# esp-oled-thing.net
KiCad netlist of a schematic drawn in EAGLE
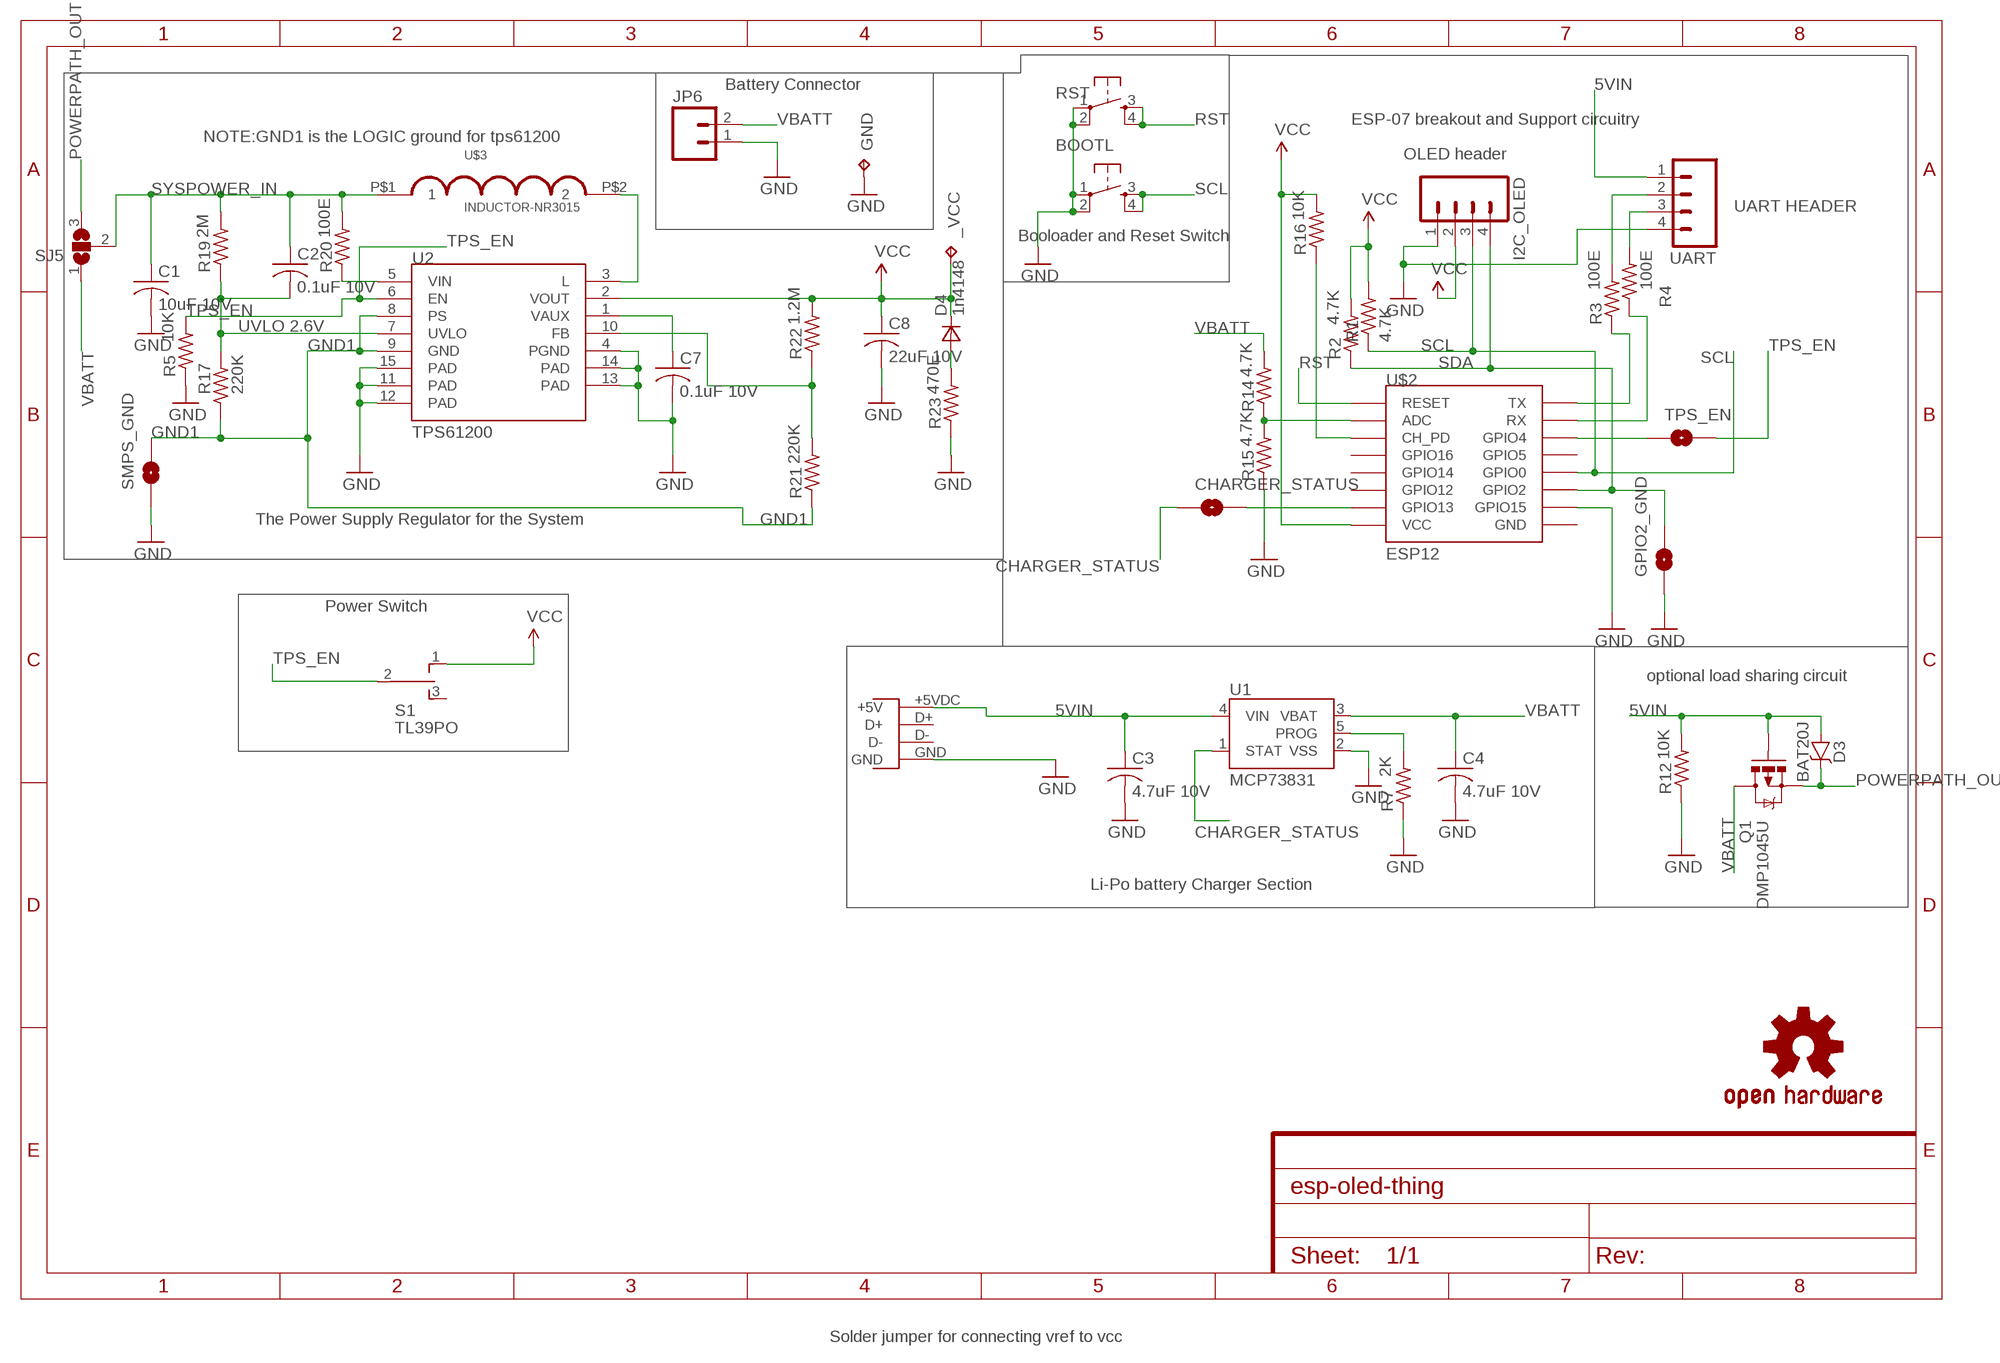
[diagram p0: schematic, sheet 1]

(export (version "E")
  (design (tool "Eeschema 10.0.6"))
  (components
    (comp (ref "BOOTL")
      (value "TAC_SWITCHSMD")
      (footprint "eagle-import:TACTILE_SWITCH_SMD")
      (libsource (lib "eagle-import") (part "TAC_SWITCHSMD"))
    )
    (comp (ref "C1")
      (value "10uF 10V")
      (footprint "eagle-import:C0805")
      (libsource (lib "eagle-import") (part "C-USC0805"))
    )
    (comp (ref "C2")
      (value "0.1uF 10V")
      (footprint "eagle-import:C0805")
      (libsource (lib "eagle-import") (part "C-USC0805"))
    )
    (comp (ref "C3")
      (value "4.7uF 10V")
      (footprint "eagle-import:C0805")
      (libsource (lib "eagle-import") (part "C-USC0805"))
    )
    (comp (ref "C4")
      (value "4.7uF 10V")
      (footprint "eagle-import:C0805")
      (libsource (lib "eagle-import") (part "C-USC0805"))
    )
    (comp (ref "C7")
      (value "0.1uF 10V")
      (footprint "eagle-import:C0805")
      (libsource (lib "eagle-import") (part "C-USC0805"))
    )
    (comp (ref "C8")
      (value "22uF 10V")
      (footprint "eagle-import:C0805")
      (libsource (lib "eagle-import") (part "C-USC0805"))
    )
    (comp (ref "CHARGER_STATUS")
      (value "SOLDERJUMPERNO")
      (footprint "eagle-import:SJ_2S-NO")
      (libsource (lib "eagle-import") (part "SOLDERJUMPERNO"))
    )
    (comp (ref "D3")
      (value "BAT20J")
      (footprint "eagle-import:SOD-323")
      (libsource (lib "eagle-import") (part "DIODE-SCHOTTKY-BAT20J"))
    )
    (comp (ref "D4")
      (value "1n4148")
      (footprint "eagle-import:SOD323")
      (fields (field (name "MPN") "CDSOD323-T05C"))
      (libsource (lib "eagle-import") (part "DSOD323"))
    )
    (comp (ref "GND")
      (value "TPTP10R")
      (footprint "eagle-import:TP10R")
      (libsource (lib "eagle-import") (part "TPTP10R"))
    )
    (comp (ref "GPIO2_GND")
      (value "SOLDERJUMPERNO")
      (footprint "eagle-import:SJ_2S-NO")
      (libsource (lib "eagle-import") (part "SOLDERJUMPERNO"))
    )
    (comp (ref "I2C_OLED")
      (value "M04PTH")
      (footprint "eagle-import:1X04")
      (libsource (lib "eagle-import") (part "M04PTH"))
    )
    (comp (ref "JP6")
      (value "M02JST-PTH-2")
      (footprint "eagle-import:JST-2-PTH")
      (libsource (lib "eagle-import") (part "M02JST-PTH-2"))
    )
    (comp (ref "Q1")
      (value "DMP1045U")
      (footprint "eagle-import:SOT23-3")
      (libsource (lib "eagle-import") (part "MOSFET-PCHANNELDMG2307L"))
    )
    (comp (ref "R1")
      (value "4.7K")
      (footprint "eagle-import:M0805")
      (libsource (lib "eagle-import") (part "R-US_M0805"))
    )
    (comp (ref "R2")
      (value "4.7K")
      (footprint "eagle-import:M0805")
      (libsource (lib "eagle-import") (part "R-US_M0805"))
    )
    (comp (ref "R3")
      (value "100E")
      (footprint "eagle-import:M0805")
      (libsource (lib "eagle-import") (part "R-US_M0805"))
    )
    (comp (ref "R4")
      (value "100E")
      (footprint "eagle-import:M0805")
      (libsource (lib "eagle-import") (part "R-US_M0805"))
    )
    (comp (ref "R5")
      (value "10K")
      (footprint "eagle-import:M0805")
      (libsource (lib "eagle-import") (part "R-US_M0805"))
    )
    (comp (ref "R7")
      (value "2K")
      (footprint "eagle-import:M0805")
      (libsource (lib "eagle-import") (part "R-US_M0805"))
    )
    (comp (ref "R12")
      (value "10K")
      (footprint "eagle-import:M0805")
      (libsource (lib "eagle-import") (part "R-US_M0805"))
    )
    (comp (ref "R14")
      (value "4.7K")
      (footprint "eagle-import:M0805")
      (libsource (lib "eagle-import") (part "R-US_M0805"))
    )
    (comp (ref "R15")
      (value "4.7K")
      (footprint "eagle-import:M0805")
      (libsource (lib "eagle-import") (part "R-US_M0805"))
    )
    (comp (ref "R16")
      (value "10K")
      (footprint "eagle-import:M0805")
      (libsource (lib "eagle-import") (part "R-US_M0805"))
    )
    (comp (ref "R17")
      (value "220K")
      (footprint "eagle-import:M0805")
      (libsource (lib "eagle-import") (part "R-US_M0805"))
    )
    (comp (ref "R19")
      (value "2M")
      (footprint "eagle-import:M0805")
      (libsource (lib "eagle-import") (part "R-US_M0805"))
    )
    (comp (ref "R20")
      (value "100E")
      (footprint "eagle-import:M0805")
      (libsource (lib "eagle-import") (part "R-US_M0805"))
    )
    (comp (ref "R21")
      (value "220K")
      (footprint "eagle-import:M0805")
      (libsource (lib "eagle-import") (part "R-US_M0805"))
    )
    (comp (ref "R22")
      (value "1.2M")
      (footprint "eagle-import:M0805")
      (libsource (lib "eagle-import") (part "R-US_M0805"))
    )
    (comp (ref "R23")
      (value "470E")
      (footprint "eagle-import:M0805")
      (libsource (lib "eagle-import") (part "R-US_M0805"))
    )
    (comp (ref "RST")
      (value "TAC_SWITCHSMD")
      (footprint "eagle-import:TACTILE_SWITCH_SMD")
      (libsource (lib "eagle-import") (part "TAC_SWITCHSMD"))
    )
    (comp (ref "S1")
      (value "TL39PO")
      (footprint "eagle-import:TL3XPO")
      (libsource (lib "eagle-import") (part "TL39PO"))
    )
    (comp (ref "SJ5")
      (value "SJ2W")
      (footprint "eagle-import:SJ_2")
      (libsource (lib "eagle-import") (part "SJ2W"))
    )
    (comp (ref "SMPS_GND")
      (value "SOLDERJUMPERNO")
      (footprint "eagle-import:SJ_2S-NO")
      (libsource (lib "eagle-import") (part "SOLDERJUMPERNO"))
    )
    (comp (ref "TPS_EN")
      (value "SOLDERJUMPERNO")
      (footprint "eagle-import:SJ_2S-NO")
      (libsource (lib "eagle-import") (part "SOLDERJUMPERNO"))
    )
    (comp (ref "U$1")
      (value "OSHW-LOGOS")
      (footprint "eagle-import:OSHW-LOGO-S")
      (libsource (lib "eagle-import") (part "OSHW-LOGOS"))
    )
    (comp (ref "U$2")
      (value "ESP12")
      (footprint "eagle-import:ESP12")
      (libsource (lib "eagle-import") (part "ESP12"))
    )
    (comp (ref "U$3")
      (value "INDUCTOR-NR3015")
      (footprint "eagle-import:INDUCTOR-NR3015")
      (libsource (lib "eagle-import") (part "INDUCTOR-NR3015"))
    )
    (comp (ref "U$4")
      (value "MICROUSB-MIDMOUNT")
      (footprint "eagle-import:MICROUSB-MIDMOUNT-MOLEX")
      (libsource (lib "eagle-import") (part "MICROUSB-MIDMOUNT"))
    )
    (comp (ref "U1")
      (value "MCP73831")
      (footprint "eagle-import:SOT23-5")
      (libsource (lib "eagle-import") (part "MCP73831"))
    )
    (comp (ref "U2")
      (value "TPS61200")
      (footprint "eagle-import:QFN-10_PAD")
      (libsource (lib "eagle-import") (part "TPS61200"))
    )
    (comp (ref "UART")
      (value "M04LONGPADS")
      (footprint "eagle-import:1X04_LONGPADS")
      (libsource (lib "eagle-import") (part "M04LONGPADS"))
    )
    (comp (ref "_VCC")
      (value "TPTP10R")
      (footprint "eagle-import:TP10R")
      (libsource (lib "eagle-import") (part "TPTP10R"))
    )
  )
  (nets
    (net (code "1") (name "/5VIN") (class "Default")
      (node (ref "C3") (pin "1") (pinfunction "1_1") (pintype "passive"))
      (node (ref "D3") (pin "A") (pinfunction "A_A") (pintype "passive"))
      (node (ref "Q1") (pin "1") (pinfunction "G_1") (pintype "passive"))
      (node (ref "R12") (pin "2") (pinfunction "2_2") (pintype "passive"))
      (node (ref "U$4") (pin "+5VDC") (pinfunction "+5V_+5VDC") (pintype "bidirectional"))
      (node (ref "U1") (pin "4") (pinfunction "VIN_4") (pintype "power_in"))
      (node (ref "UART") (pin "1") (pinfunction "1_1") (pintype "passive"))
    )
    (net (code "2") (name "/CHARGER_STATUS") (class "Default")
      (node (ref "CHARGER_STATUS") (pin "1") (pinfunction "1_1") (pintype "passive"))
      (node (ref "U1") (pin "1") (pinfunction "STAT_1") (pintype "output"))
    )
    (net (code "3") (name "/GND1") (class "Default")
      (node (ref "R17") (pin "1") (pinfunction "1_1") (pintype "passive"))
      (node (ref "R21") (pin "1") (pinfunction "1_1") (pintype "passive"))
      (node (ref "SMPS_GND") (pin "2") (pinfunction "2_2") (pintype "passive"))
      (node (ref "U2") (pin "8") (pinfunction "PS_8") (pintype "input"))
      (node (ref "U2") (pin "9") (pinfunction "GND_9") (pintype "power_in"))
    )
    (net (code "4") (name "/POWERPATH_OUT") (class "Default")
      (node (ref "D3") (pin "C") (pinfunction "C_C") (pintype "passive"))
      (node (ref "Q1") (pin "2") (pinfunction "S_2") (pintype "passive"))
      (node (ref "SJ5") (pin "3") (pinfunction "3_3") (pintype "passive"))
    )
    (net (code "5") (name "/RST") (class "Default")
      (node (ref "RST") (pin "3") (pinfunction "3_3") (pintype "passive"))
      (node (ref "RST") (pin "4") (pinfunction "4_4") (pintype "passive"))
      (node (ref "U$2") (pin "RESET") (pinfunction "RESET_RESET") (pintype "bidirectional"))
    )
    (net (code "6") (name "/SCL") (class "Default")
      (node (ref "BOOTL") (pin "3") (pinfunction "3_3") (pintype "passive"))
      (node (ref "BOOTL") (pin "4") (pinfunction "4_4") (pintype "passive"))
      (node (ref "I2C_OLED") (pin "3") (pinfunction "3_3") (pintype "passive"))
      (node (ref "R1") (pin "1") (pinfunction "1_1") (pintype "passive"))
      (node (ref "U$2") (pin "GPIO0") (pinfunction "GPIO0_GPIO0") (pintype "bidirectional"))
    )
    (net (code "7") (name "/SDA") (class "Default")
      (node (ref "GPIO2_GND") (pin "2") (pinfunction "2_2") (pintype "passive"))
      (node (ref "I2C_OLED") (pin "4") (pinfunction "4_4") (pintype "passive"))
      (node (ref "R2") (pin "1") (pinfunction "1_1") (pintype "passive"))
      (node (ref "U$2") (pin "GPIO2") (pinfunction "GPIO2_GPIO2") (pintype "bidirectional"))
    )
    (net (code "8") (name "/SYSPOWER_IN") (class "Default")
      (node (ref "C1") (pin "1") (pinfunction "1_1") (pintype "passive"))
      (node (ref "C2") (pin "1") (pinfunction "1_1") (pintype "passive"))
      (node (ref "R19") (pin "2") (pinfunction "2_2") (pintype "passive"))
      (node (ref "R20") (pin "2") (pinfunction "2_2") (pintype "passive"))
      (node (ref "SJ5") (pin "2") (pinfunction "2_2") (pintype "passive"))
      (node (ref "U$3") (pin "P$1") (pinfunction "1_P$1") (pintype "bidirectional"))
    )
    (net (code "9") (name "/TPS_EN") (class "Default")
      (node (ref "R5") (pin "2") (pinfunction "2_2") (pintype "passive"))
      (node (ref "S1") (pin "2") (pinfunction "P_2") (pintype "passive"))
      (node (ref "TPS_EN") (pin "2") (pinfunction "2_2") (pintype "passive"))
      (node (ref "U2") (pin "6") (pinfunction "EN_6") (pintype "input"))
    )
    (net (code "10") (name "/VBATT") (class "Default")
      (node (ref "C4") (pin "1") (pinfunction "1_1") (pintype "passive"))
      (node (ref "JP6") (pin "2") (pinfunction "2_2") (pintype "passive"))
      (node (ref "Q1") (pin "3") (pinfunction "D_3") (pintype "passive"))
      (node (ref "R14") (pin "2") (pinfunction "2_2") (pintype "passive"))
      (node (ref "SJ5") (pin "1") (pinfunction "1_1") (pintype "passive"))
      (node (ref "U1") (pin "3") (pinfunction "VBAT_3") (pintype "power_in"))
    )
    (net (code "11") (name "GND") (class "Default")
      (node (ref "BOOTL") (pin "1") (pinfunction "1_1") (pintype "passive"))
      (node (ref "BOOTL") (pin "2") (pinfunction "2_2") (pintype "passive"))
      (node (ref "C1") (pin "2") (pinfunction "2_2") (pintype "passive"))
      (node (ref "C3") (pin "2") (pinfunction "2_2") (pintype "passive"))
      (node (ref "C4") (pin "2") (pinfunction "2_2") (pintype "passive"))
      (node (ref "C7") (pin "2") (pinfunction "2_2") (pintype "passive"))
      (node (ref "C8") (pin "2") (pinfunction "2_2") (pintype "passive"))
      (node (ref "GND") (pin "TP") (pinfunction "TP_TP") (pintype "input"))
      (node (ref "GPIO2_GND") (pin "1") (pinfunction "1_1") (pintype "passive"))
      (node (ref "I2C_OLED") (pin "1") (pinfunction "1_1") (pintype "passive"))
      (node (ref "JP6") (pin "1") (pinfunction "1_1") (pintype "passive"))
      (node (ref "R12") (pin "1") (pinfunction "1_1") (pintype "passive"))
      (node (ref "R15") (pin "1") (pinfunction "1_1") (pintype "passive"))
      (node (ref "R23") (pin "1") (pinfunction "1_1") (pintype "passive"))
      (node (ref "R5") (pin "1") (pinfunction "1_1") (pintype "passive"))
      (node (ref "R7") (pin "1") (pinfunction "1_1") (pintype "passive"))
      (node (ref "RST") (pin "1") (pinfunction "1_1") (pintype "passive"))
      (node (ref "RST") (pin "2") (pinfunction "2_2") (pintype "passive"))
      (node (ref "SMPS_GND") (pin "1") (pinfunction "1_1") (pintype "passive"))
      (node (ref "U$2") (pin "GPIO15") (pinfunction "GPIO15_GPIO15") (pintype "bidirectional"))
      (node (ref "U$4") (pin "GND") (pinfunction "GND_GND") (pintype "bidirectional"))
      (node (ref "U1") (pin "2") (pinfunction "VSS_2") (pintype "power_in"))
      (node (ref "U2") (pin "11") (pinfunction "PAD_11") (pintype "power_in"))
      (node (ref "U2") (pin "12") (pinfunction "PAD_12") (pintype "power_in"))
      (node (ref "U2") (pin "13") (pinfunction "PAD_13") (pintype "power_in"))
      (node (ref "U2") (pin "14") (pinfunction "PAD_14") (pintype "power_in"))
      (node (ref "U2") (pin "15") (pinfunction "PAD_15") (pintype "power_in"))
      (node (ref "U2") (pin "4") (pinfunction "PGND_4") (pintype "power_in"))
      (node (ref "UART") (pin "4") (pinfunction "4_4") (pintype "passive"))
    )
    (net (code "12") (name "Net-(CHARGER_STATUS-Pad2)") (class "Default")
      (node (ref "CHARGER_STATUS") (pin "2") (pinfunction "2_2") (pintype "passive"))
      (node (ref "U$2") (pin "GPIO13") (pinfunction "GPIO13_GPIO13") (pintype "bidirectional"))
    )
    (net (code "13") (name "Net-(D4-A)") (class "Default")
      (node (ref "D4") (pin "2") (pinfunction "A_2") (pintype "passive"))
      (node (ref "R23") (pin "2") (pinfunction "2_2") (pintype "passive"))
    )
    (net (code "14") (name "Net-(R3-Pad1)") (class "Default")
      (node (ref "R3") (pin "1") (pinfunction "1_1") (pintype "passive"))
      (node (ref "U$2") (pin "TX") (pinfunction "TX_TX") (pintype "bidirectional"))
    )
    (net (code "15") (name "Net-(R3-Pad2)") (class "Default")
      (node (ref "R3") (pin "2") (pinfunction "2_2") (pintype "passive"))
      (node (ref "UART") (pin "2") (pinfunction "2_2") (pintype "passive"))
    )
    (net (code "16") (name "Net-(R4-Pad1)") (class "Default")
      (node (ref "R4") (pin "1") (pinfunction "1_1") (pintype "passive"))
      (node (ref "U$2") (pin "RX") (pinfunction "RX_RX") (pintype "bidirectional"))
    )
    (net (code "17") (name "Net-(R4-Pad2)") (class "Default")
      (node (ref "R4") (pin "2") (pinfunction "2_2") (pintype "passive"))
      (node (ref "UART") (pin "3") (pinfunction "3_3") (pintype "passive"))
    )
    (net (code "18") (name "Net-(R14-Pad1)") (class "Default")
      (node (ref "R14") (pin "1") (pinfunction "1_1") (pintype "passive"))
      (node (ref "R15") (pin "2") (pinfunction "2_2") (pintype "passive"))
      (node (ref "U$2") (pin "ADC") (pinfunction "ADC_ADC") (pintype "bidirectional"))
    )
    (net (code "19") (name "Net-(R16-Pad1)") (class "Default")
      (node (ref "R16") (pin "1") (pinfunction "1_1") (pintype "passive"))
      (node (ref "U$2") (pin "CH_PD") (pinfunction "CH_PD_CH_PD") (pintype "bidirectional"))
    )
    (net (code "20") (name "Net-(TPS_EN-Pad1)") (class "Default")
      (node (ref "TPS_EN") (pin "1") (pinfunction "1_1") (pintype "passive"))
      (node (ref "U$2") (pin "GPIO4") (pinfunction "GPIO4_GPIO4") (pintype "bidirectional"))
    )
    (net (code "21") (name "Net-(U$3-2)") (class "Default")
      (node (ref "U$3") (pin "P$2") (pinfunction "2_P$2") (pintype "bidirectional"))
      (node (ref "U2") (pin "3") (pinfunction "L_3") (pintype "passive"))
    )
    (net (code "22") (name "Net-(U1-PROG)") (class "Default")
      (node (ref "R7") (pin "2") (pinfunction "2_2") (pintype "passive"))
      (node (ref "U1") (pin "5") (pinfunction "PROG_5") (pintype "input"))
    )
    (net (code "23") (name "Net-(U2-FB)") (class "Default")
      (node (ref "R21") (pin "2") (pinfunction "2_2") (pintype "passive"))
      (node (ref "R22") (pin "1") (pinfunction "1_1") (pintype "passive"))
      (node (ref "U2") (pin "10") (pinfunction "FB_10") (pintype "passive"))
    )
    (net (code "24") (name "Net-(U2-UVLO)") (class "Default")
      (node (ref "C2") (pin "2") (pinfunction "2_2") (pintype "passive"))
      (node (ref "R17") (pin "2") (pinfunction "2_2") (pintype "passive"))
      (node (ref "R19") (pin "1") (pinfunction "1_1") (pintype "passive"))
      (node (ref "U2") (pin "7") (pinfunction "UVLO_7") (pintype "passive"))
    )
    (net (code "25") (name "Net-(U2-VAUX)") (class "Default")
      (node (ref "C7") (pin "1") (pinfunction "1_1") (pintype "passive"))
      (node (ref "U2") (pin "1") (pinfunction "VAUX_1") (pintype "passive"))
    )
    (net (code "26") (name "Net-(U2-VIN)") (class "Default")
      (node (ref "R20") (pin "1") (pinfunction "1_1") (pintype "passive"))
      (node (ref "U2") (pin "5") (pinfunction "VIN_5") (pintype "power_in"))
    )
    (net (code "27") (name "VCC") (class "Default")
      (node (ref "C8") (pin "1") (pinfunction "1_1") (pintype "passive"))
      (node (ref "D4") (pin "1") (pinfunction "C_1") (pintype "passive"))
      (node (ref "I2C_OLED") (pin "2") (pinfunction "2_2") (pintype "passive"))
      (node (ref "R1") (pin "2") (pinfunction "2_2") (pintype "passive"))
      (node (ref "R16") (pin "2") (pinfunction "2_2") (pintype "passive"))
      (node (ref "R2") (pin "2") (pinfunction "2_2") (pintype "passive"))
      (node (ref "R22") (pin "2") (pinfunction "2_2") (pintype "passive"))
      (node (ref "S1") (pin "1") (pinfunction "O_1") (pintype "passive"))
      (node (ref "U$2") (pin "VCC") (pinfunction "VCC_VCC") (pintype "bidirectional"))
      (node (ref "U2") (pin "2") (pinfunction "VOUT_2") (pintype "passive"))
      (node (ref "_VCC") (pin "TP") (pinfunction "TP_TP") (pintype "input"))
    )
    (net (code "28") (name "unconnected-(S1-S-Pad3)") (class "Default")
      (node (ref "S1") (pin "3") (pinfunction "S_3") (pintype "passive"))
    )
    (net (code "29") (name "unconnected-(U$2-PadGND)") (class "Default")
      (node (ref "U$2") (pin "GND") (pinfunction "GND_GND") (pintype "bidirectional"))
    )
    (net (code "30") (name "unconnected-(U$2-PadGPIO5)") (class "Default")
      (node (ref "U$2") (pin "GPIO5") (pinfunction "GPIO5_GPIO5") (pintype "bidirectional"))
    )
    (net (code "31") (name "unconnected-(U$2-PadGPIO12)") (class "Default")
      (node (ref "U$2") (pin "GPIO12") (pinfunction "GPIO12_GPIO12") (pintype "bidirectional"))
    )
    (net (code "32") (name "unconnected-(U$2-PadGPIO14)") (class "Default")
      (node (ref "U$2") (pin "GPIO14") (pinfunction "GPIO14_GPIO14") (pintype "bidirectional"))
    )
    (net (code "33") (name "unconnected-(U$2-PadGPIO16)") (class "Default")
      (node (ref "U$2") (pin "GPIO16") (pinfunction "GPIO16_GPIO16") (pintype "bidirectional"))
    )
    (net (code "34") (name "unconnected-(U$4-PadD+)") (class "Default")
      (node (ref "U$4") (pin "D+") (pinfunction "D+_D+") (pintype "bidirectional"))
    )
    (net (code "35") (name "unconnected-(U$4-PadD-)") (class "Default")
      (node (ref "U$4") (pin "D-") (pinfunction "D-_D-") (pintype "bidirectional"))
    )
  )
)
